# ESP8266-DS18B20-outside-lite.net
KiCad netlist of a schematic drawn in EAGLE
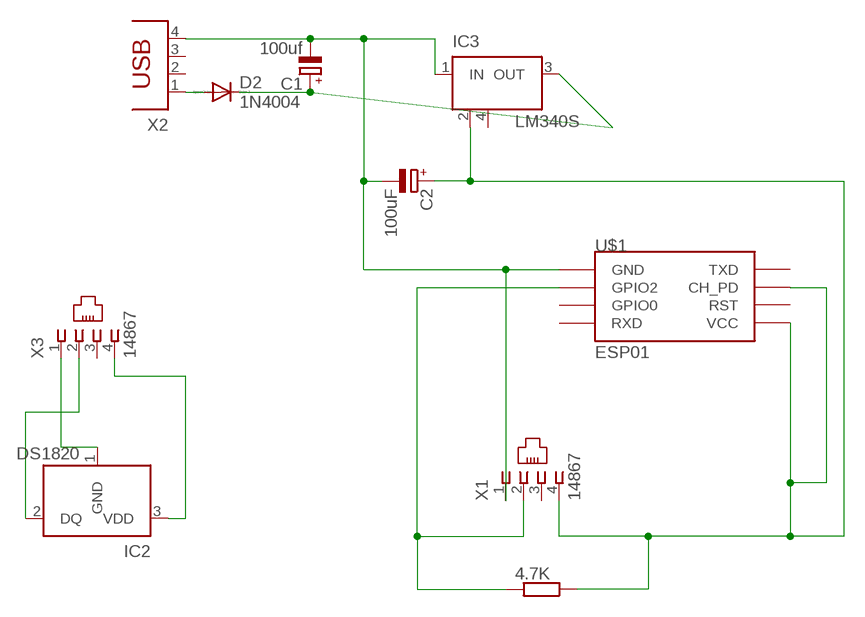
[diagram p0: schematic, sheet 1]

(export (version "E")
  (design (tool "Eeschema 10.0.6"))
  (components
    (comp (ref "4.7K")
      (value "SMK")
      (footprint "eagle-import:SMK")
      (libsource (lib "eagle-import") (part "SMK"))
    )
    (comp (ref "C1")
      (value "100uf")
      (footprint "eagle-import:E2,5-5")
      (libsource (lib "eagle-import") (part "CPOL-EUE2.5-5"))
    )
    (comp (ref "C2")
      (value "100uF")
      (footprint "eagle-import:E2,5-5")
      (libsource (lib "eagle-import") (part "CPOL-EUE2.5-5"))
    )
    (comp (ref "D2")
      (value "1N4004")
      (footprint "eagle-import:DO41-10")
      (libsource (lib "eagle-import") (part "1N4004"))
    )
    (comp (ref "IC2")
      (value "DS1820")
      (footprint "eagle-import:TO-92")
      (libsource (lib "eagle-import") (part "DS1820"))
    )
    (comp (ref "IC3")
      (value "LM340S")
      (footprint "eagle-import:SOT223")
      (libsource (lib "eagle-import") (part "LM340S"))
    )
    (comp (ref "U$1")
      (value "ESP01")
      (footprint "eagle-import:ESP01")
      (libsource (lib "eagle-import") (part "ESP01"))
    )
    (comp (ref "X1")
      (value "14867")
      (footprint "eagle-import:14867")
      (libsource (lib "eagle-import") (part "14867"))
    )
    (comp (ref "X2")
      (value "PN61729")
      (footprint "eagle-import:PN61729")
      (libsource (lib "eagle-import") (part "PN61729"))
    )
    (comp (ref "X3")
      (value "14867")
      (footprint "eagle-import:14867")
      (libsource (lib "eagle-import") (part "14867"))
    )
  )
  (nets
    (net (code "1") (name "/5V") (class "Default")
      (node (ref "C1") (pin "+") (pinfunction "+_+") (pintype "passive"))
      (node (ref "D2") (pin "A") (pinfunction "A_A") (pintype "passive"))
      (node (ref "D2") (pin "C") (pinfunction "C_C") (pintype "passive"))
      (node (ref "IC3") (pin "3") (pinfunction "OUT_3") (pintype "passive"))
      (node (ref "X2") (pin "1") (pinfunction "1_1") (pintype "passive"))
    )
    (net (code "2") (name "/GND") (class "Default")
      (node (ref "IC3") (pin "4") (pinfunction "GND_4") (pintype "power_in"))
    )
    (net (code "3") (name "Net-(4.7K-Pad1)") (class "Default")
      (node (ref "4.7K") (pin "1") (pinfunction "1_1") (pintype "passive"))
      (node (ref "C2") (pin "+") (pinfunction "+_+") (pintype "passive"))
      (node (ref "IC3") (pin "2") (pinfunction "GND_2") (pintype "power_in"))
      (node (ref "U$1") (pin "CH_PD") (pinfunction "CH_PD_CH_PD") (pintype "bidirectional"))
      (node (ref "U$1") (pin "VCC") (pinfunction "VCC_VCC") (pintype "bidirectional"))
      (node (ref "X1") (pin "4") (pinfunction "4_4") (pintype "passive"))
    )
    (net (code "4") (name "Net-(4.7K-Pad2)") (class "Default")
      (node (ref "4.7K") (pin "2") (pinfunction "2_2") (pintype "passive"))
      (node (ref "U$1") (pin "GPIO2") (pinfunction "GPIO2_GPIO2") (pintype "bidirectional"))
      (node (ref "X1") (pin "2") (pinfunction "2_2") (pintype "passive"))
    )
    (net (code "5") (name "Net-(IC2-DQ)") (class "Default")
      (node (ref "IC2") (pin "2") (pinfunction "DQ_2") (pintype "output"))
      (node (ref "X3") (pin "2") (pinfunction "2_2") (pintype "passive"))
    )
    (net (code "6") (name "Net-(IC2-GND)") (class "Default")
      (node (ref "IC2") (pin "1") (pinfunction "GND_1") (pintype "power_in"))
      (node (ref "X3") (pin "1") (pinfunction "1_1") (pintype "passive"))
    )
    (net (code "7") (name "Net-(IC2-VDD)") (class "Default")
      (node (ref "IC2") (pin "3") (pinfunction "VDD_3") (pintype "input"))
      (node (ref "X3") (pin "4") (pinfunction "4_4") (pintype "passive"))
    )
    (net (code "8") (name "Net-(IC3-IN)") (class "Default")
      (node (ref "C1") (pin "-") (pinfunction "-_-") (pintype "passive"))
      (node (ref "C2") (pin "-") (pinfunction "-_-") (pintype "passive"))
      (node (ref "IC3") (pin "1") (pinfunction "IN_1") (pintype "input"))
      (node (ref "U$1") (pin "GND") (pinfunction "GND_GND") (pintype "bidirectional"))
      (node (ref "X1") (pin "1") (pinfunction "1_1") (pintype "passive"))
      (node (ref "X2") (pin "4") (pinfunction "4_4") (pintype "passive"))
    )
    (net (code "9") (name "unconnected-(U$1-PadGPIO0)") (class "Default")
      (node (ref "U$1") (pin "GPIO0") (pinfunction "GPIO0_GPIO0") (pintype "bidirectional"))
    )
    (net (code "10") (name "unconnected-(U$1-PadRST)") (class "Default")
      (node (ref "U$1") (pin "RST") (pinfunction "RST_RST") (pintype "bidirectional"))
    )
    (net (code "11") (name "unconnected-(U$1-RXD-PadRX)") (class "Default")
      (node (ref "U$1") (pin "RX") (pinfunction "RXD_RX") (pintype "bidirectional"))
    )
    (net (code "12") (name "unconnected-(U$1-TXD-PadTX)") (class "Default")
      (node (ref "U$1") (pin "TX") (pinfunction "TXD_TX") (pintype "bidirectional"))
    )
    (net (code "13") (name "unconnected-(X1-Pad3)") (class "Default")
      (node (ref "X1") (pin "3") (pinfunction "3_3") (pintype "passive"))
    )
    (net (code "14") (name "unconnected-(X2-Pad2)") (class "Default")
      (node (ref "X2") (pin "2") (pinfunction "2_2") (pintype "passive"))
    )
    (net (code "15") (name "unconnected-(X2-Pad3)") (class "Default")
      (node (ref "X2") (pin "3") (pinfunction "3_3") (pintype "passive"))
    )
    (net (code "16") (name "unconnected-(X3-Pad3)") (class "Default")
      (node (ref "X3") (pin "3") (pinfunction "3_3") (pintype "passive"))
    )
  )
)
